# bulb.net
KiCad netlist of a schematic drawn in EAGLE
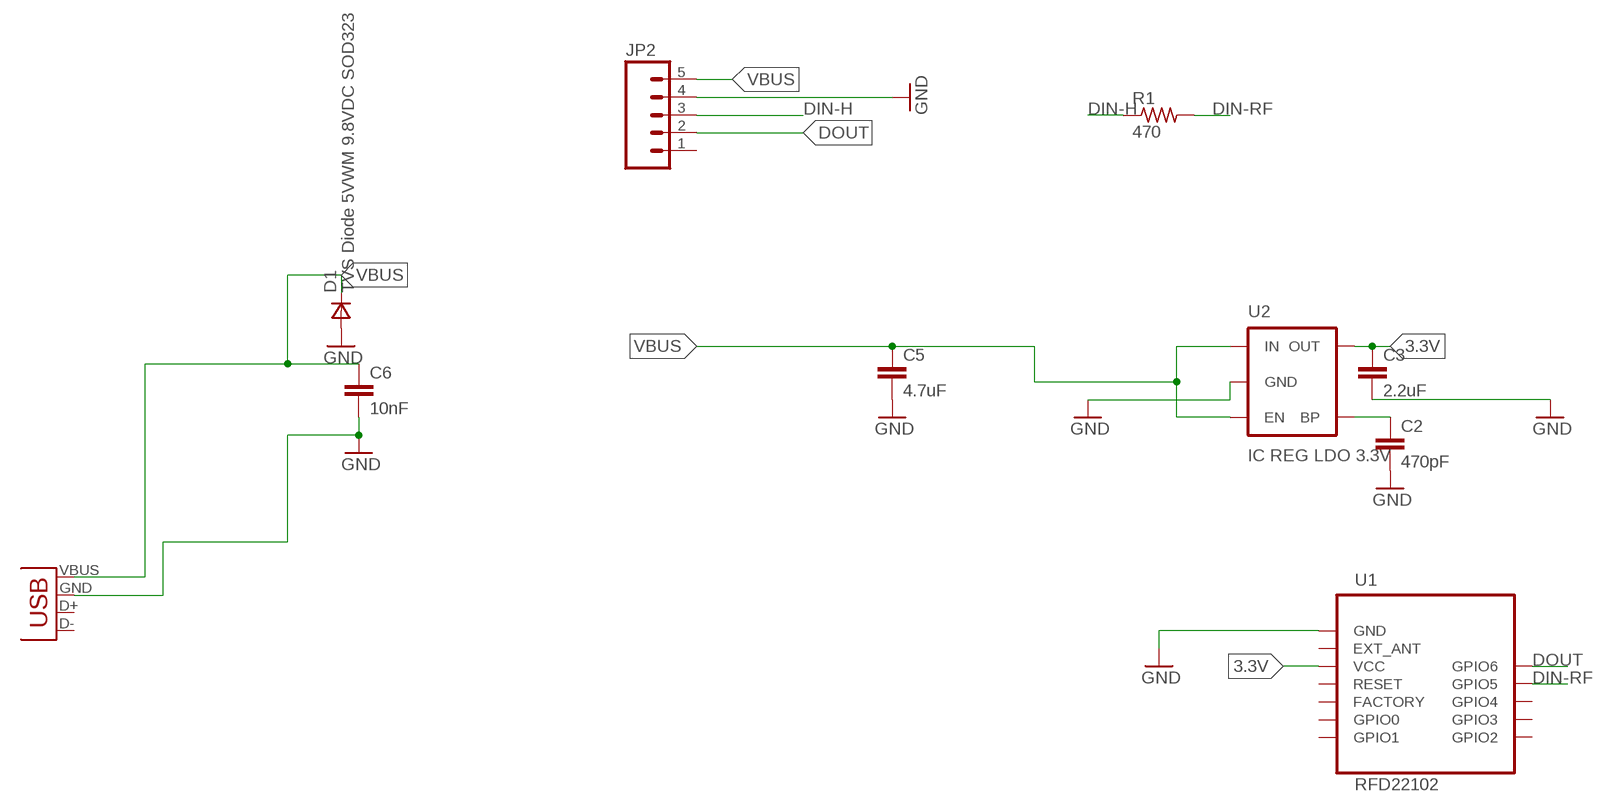
[diagram p0: schematic, sheet 1]

(export (version "E")
  (design (tool "Eeschema 10.0.6"))
  (components
    (comp (ref "C2")
      (value "470pF")
      (footprint "eagle-import:0603-CAP")
      (libsource (lib "eagle-import") (part "470PF-50V-5%(0603)SMD"))
    )
    (comp (ref "C3")
      (value "2.2uF")
      (footprint "eagle-import:0603-CAP")
      (libsource (lib "eagle-import") (part "2.2UF-10V-20%(0603)"))
    )
    (comp (ref "C5")
      (value "4.7uF")
      (footprint "eagle-import:0603-CAP")
      (libsource (lib "eagle-import") (part "4.7UF-6.3V-10%(0603)0603"))
    )
    (comp (ref "C6")
      (value "10nF")
      (footprint "eagle-import:0603-CAP")
      (libsource (lib "eagle-import") (part "10NF/10000PF-50V-10%(0603)"))
    )
    (comp (ref "D1")
      (value "TVS Diode 5VWM 9.8VDC SOD323")
      (footprint "eagle-import:SOD323")
      (fields (field (name "MPN") "CDSOD323-T05C"))
      (libsource (lib "eagle-import") (part "DSOD323"))
    )
    (comp (ref "JP1")
      (value "USB-A-H")
      (footprint "eagle-import:USB-A-H")
      (libsource (lib "eagle-import") (part "USB-A-H"))
    )
    (comp (ref "JP2")
      (value "M05PTH")
      (footprint "eagle-import:1X05")
      (libsource (lib "eagle-import") (part "M05PTH"))
    )
    (comp (ref "R1")
      (value "470")
      (footprint "eagle-import:R0603")
      (libsource (lib "eagle-import") (part "R-US_R0603"))
    )
    (comp (ref "U1")
      (value "RFD22102")
      (footprint "eagle-import:RFD22102")
      (libsource (lib "eagle-import") (part "RFD22102"))
    )
    (comp (ref "U2")
      (value "IC REG LDO 3.3V")
      (footprint "eagle-import:SOT23-5")
      (libsource (lib "eagle-import") (part "MIC52053.3V"))
    )
  )
  (nets
    (net (code "1") (name "/DIN-H") (class "Default")
      (node (ref "JP2") (pin "3") (pinfunction "3_3") (pintype "passive"))
      (node (ref "R1") (pin "1") (pinfunction "1_1") (pintype "passive"))
    )
    (net (code "2") (name "/DIN-RF") (class "Default")
      (node (ref "R1") (pin "2") (pinfunction "2_2") (pintype "passive"))
      (node (ref "U1") (pin "GPIO5") (pinfunction "GPIO5_GPIO5") (pintype "bidirectional"))
    )
    (net (code "3") (name "3.3V") (class "Default")
      (node (ref "C3") (pin "1") (pinfunction "1_1") (pintype "passive"))
      (node (ref "U1") (pin "VCC") (pinfunction "VCC_VCC") (pintype "power_in"))
      (node (ref "U2") (pin "5") (pinfunction "OUT_5") (pintype "passive"))
    )
    (net (code "4") (name "DOUT") (class "Default")
      (node (ref "JP2") (pin "2") (pinfunction "2_2") (pintype "passive"))
      (node (ref "U1") (pin "GPIO6") (pinfunction "GPIO6_GPIO6") (pintype "bidirectional"))
    )
    (net (code "5") (name "GND") (class "Default")
      (node (ref "C2") (pin "2") (pinfunction "2_2") (pintype "passive"))
      (node (ref "C3") (pin "2") (pinfunction "2_2") (pintype "passive"))
      (node (ref "C5") (pin "2") (pinfunction "2_2") (pintype "passive"))
      (node (ref "C6") (pin "2") (pinfunction "2_2") (pintype "passive"))
      (node (ref "D1") (pin "2") (pinfunction "A_2") (pintype "passive"))
      (node (ref "JP1") (pin "GND") (pinfunction "VBUS_GND") (pintype "bidirectional"))
      (node (ref "JP2") (pin "4") (pinfunction "4_4") (pintype "passive"))
      (node (ref "U1") (pin "GND") (pinfunction "GND_GND") (pintype "power_in"))
      (node (ref "U2") (pin "2") (pinfunction "GND_2") (pintype "input"))
    )
    (net (code "6") (name "Net-(U2-BP)") (class "Default")
      (node (ref "C2") (pin "1") (pinfunction "1_1") (pintype "passive"))
      (node (ref "U2") (pin "4") (pinfunction "BP_4") (pintype "input"))
    )
    (net (code "7") (name "VBUS") (class "Default")
      (node (ref "C5") (pin "1") (pinfunction "1_1") (pintype "passive"))
      (node (ref "C6") (pin "1") (pinfunction "1_1") (pintype "passive"))
      (node (ref "D1") (pin "1") (pinfunction "C_1") (pintype "passive"))
      (node (ref "JP1") (pin "VBUS") (pinfunction "GND_VBUS") (pintype "bidirectional"))
      (node (ref "JP2") (pin "5") (pinfunction "5_5") (pintype "passive"))
      (node (ref "U2") (pin "1") (pinfunction "IN_1") (pintype "input"))
      (node (ref "U2") (pin "3") (pinfunction "EN_3") (pintype "input"))
    )
    (net (code "8") (name "unconnected-(JP1-D+-PadD-)") (class "Default")
      (node (ref "JP1") (pin "D-") (pinfunction "D+_D-") (pintype "bidirectional"))
    )
    (net (code "9") (name "unconnected-(JP1-D--PadD+)") (class "Default")
      (node (ref "JP1") (pin "D+") (pinfunction "D-_D+") (pintype "bidirectional"))
    )
    (net (code "10") (name "unconnected-(JP2-Pad1)") (class "Default")
      (node (ref "JP2") (pin "1") (pinfunction "1_1") (pintype "passive"))
    )
    (net (code "11") (name "unconnected-(U1-PadEXT_ANT)") (class "Default")
      (node (ref "U1") (pin "EXT_ANT") (pinfunction "EXT_ANT_EXT_ANT") (pintype "no_connect"))
    )
    (net (code "12") (name "unconnected-(U1-PadFACTORY)") (class "Default")
      (node (ref "U1") (pin "FACTORY") (pinfunction "FACTORY_FACTORY") (pintype "bidirectional"))
    )
    (net (code "13") (name "unconnected-(U1-PadGPIO0)") (class "Default")
      (node (ref "U1") (pin "GPIO0") (pinfunction "GPIO0_GPIO0") (pintype "bidirectional"))
    )
    (net (code "14") (name "unconnected-(U1-PadGPIO1)") (class "Default")
      (node (ref "U1") (pin "GPIO1") (pinfunction "GPIO1_GPIO1") (pintype "bidirectional"))
    )
    (net (code "15") (name "unconnected-(U1-PadGPIO2)") (class "Default")
      (node (ref "U1") (pin "GPIO2") (pinfunction "GPIO2_GPIO2") (pintype "bidirectional"))
    )
    (net (code "16") (name "unconnected-(U1-PadGPIO3)") (class "Default")
      (node (ref "U1") (pin "GPIO3") (pinfunction "GPIO3_GPIO3") (pintype "bidirectional"))
    )
    (net (code "17") (name "unconnected-(U1-PadGPIO4)") (class "Default")
      (node (ref "U1") (pin "GPIO4") (pinfunction "GPIO4_GPIO4") (pintype "bidirectional"))
    )
    (net (code "18") (name "unconnected-(U1-PadRESET)") (class "Default")
      (node (ref "U1") (pin "RESET") (pinfunction "RESET_RESET") (pintype "bidirectional"))
    )
  )
)
